# ESP32_PSU.net
KiCad netlist of a schematic drawn in EAGLE
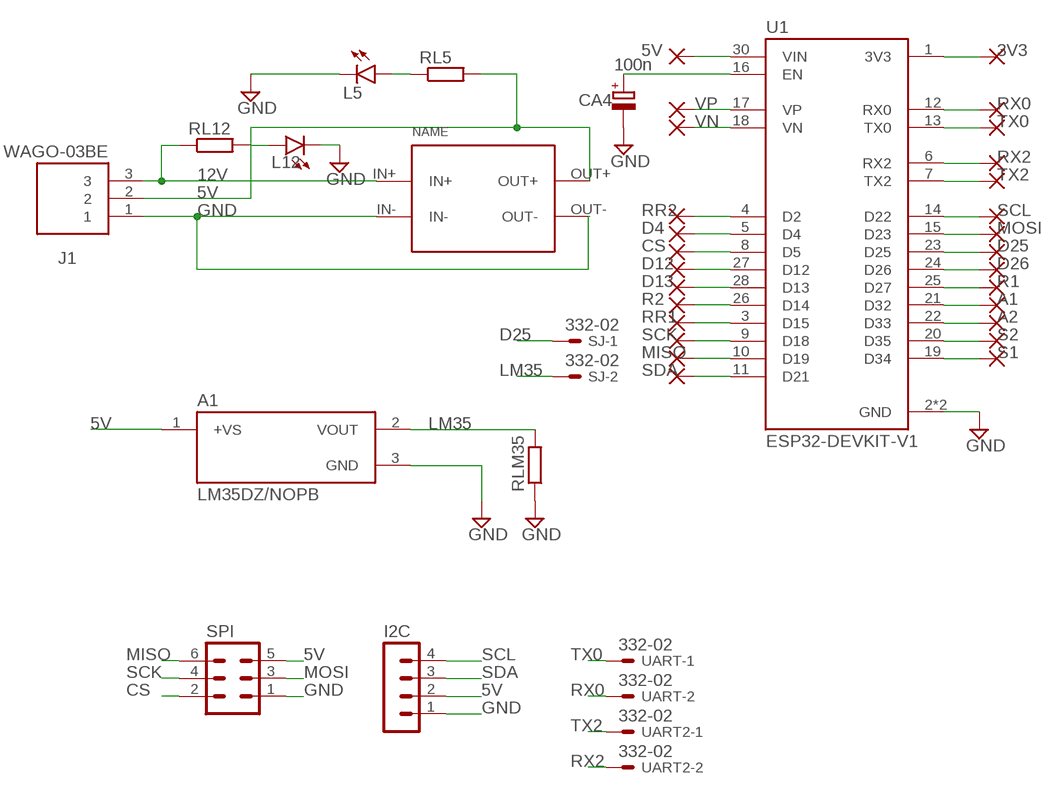
[diagram p0: schematic, sheet 1]

(export (version "E")
  (design (tool "Eeschema 10.0.6"))
  (components
    (comp (ref "A1")
      (value "LM35DZ/NOPB")
      (footprint "eagle-import:TO92127P521H735-3")
      (fields (field (name "DIGIKEY_PART_NUMBER") "LM35DZ/NOPB-ND") (field (name "MF") "Texas"))
      (libsource (lib "eagle-import") (part "LM35DZ/NOPB"))
    )
    (comp (ref "CA4")
      (value "100n")
      (footprint "eagle-import:E5-6")
      (libsource (lib "eagle-import") (part "CPOL-EUE5-6"))
    )
    (comp (ref "I2C")
      (value "MA04-1")
      (footprint "eagle-import:MA04-1")
      (libsource (lib "eagle-import") (part "MA04-1"))
    )
    (comp (ref "J1")
      (value "WAGO-03BE")
      (footprint "eagle-import:CUI_TB006-508-03BE")
      (fields (field (name "MF") "Same Sky") (field (name "MP") "TB006-508-03BE"))
      (libsource (lib "eagle-import") (part "WAGO-03BE"))
    )
    (comp (ref "L5")
      (value "LED3MM")
      (footprint "eagle-import:LED3MM")
      (libsource (lib "eagle-import") (part "LED3MM"))
    )
    (comp (ref "L12")
      (value "LED3MM")
      (footprint "eagle-import:LED3MM")
      (libsource (lib "eagle-import") (part "LED3MM"))
    )
    (comp (ref "PAD1")
      (value "WIREPAD1,6/0,9")
      (footprint "eagle-import:1,6_0,9")
      (libsource (lib "eagle-import") (part "WIREPAD1,6/0,9"))
    )
    (comp (ref "PAD2")
      (value "WIREPAD1,6/0,9")
      (footprint "eagle-import:1,6_0,9")
      (libsource (lib "eagle-import") (part "WIREPAD1,6/0,9"))
    )
    (comp (ref "PAD3")
      (value "WIREPAD1,6/0,9")
      (footprint "eagle-import:1,6_0,9")
      (libsource (lib "eagle-import") (part "WIREPAD1,6/0,9"))
    )
    (comp (ref "PAD4")
      (value "WIREPAD1,6/0,9")
      (footprint "eagle-import:1,6_0,9")
      (libsource (lib "eagle-import") (part "WIREPAD1,6/0,9"))
    )
    (comp (ref "PAD5")
      (value "WIREPAD1,6/0,9")
      (footprint "eagle-import:1,6_0,9")
      (libsource (lib "eagle-import") (part "WIREPAD1,6/0,9"))
    )
    (comp (ref "PAD6")
      (value "WIREPAD1,6/0,9")
      (footprint "eagle-import:1,6_0,9")
      (libsource (lib "eagle-import") (part "WIREPAD1,6/0,9"))
    )
    (comp (ref "PAD7")
      (value "WIREPAD1,6/0,9")
      (footprint "eagle-import:1,6_0,9")
      (libsource (lib "eagle-import") (part "WIREPAD1,6/0,9"))
    )
    (comp (ref "PAD8")
      (value "WIREPAD1,6/0,9")
      (footprint "eagle-import:1,6_0,9")
      (libsource (lib "eagle-import") (part "WIREPAD1,6/0,9"))
    )
    (comp (ref "PAD9")
      (value "WIREPAD1,6/0,9")
      (footprint "eagle-import:1,6_0,9")
      (libsource (lib "eagle-import") (part "WIREPAD1,6/0,9"))
    )
    (comp (ref "PAD10")
      (value "WIREPAD1,6/0,9")
      (footprint "eagle-import:1,6_0,9")
      (libsource (lib "eagle-import") (part "WIREPAD1,6/0,9"))
    )
    (comp (ref "PAD11")
      (value "WIREPAD1,6/0,9")
      (footprint "eagle-import:1,6_0,9")
      (libsource (lib "eagle-import") (part "WIREPAD1,6/0,9"))
    )
    (comp (ref "PAD12")
      (value "WIREPAD1,6/0,9")
      (footprint "eagle-import:1,6_0,9")
      (libsource (lib "eagle-import") (part "WIREPAD1,6/0,9"))
    )
    (comp (ref "PAD13")
      (value "WIREPAD1,6/0,9")
      (footprint "eagle-import:1,6_0,9")
      (libsource (lib "eagle-import") (part "WIREPAD1,6/0,9"))
    )
    (comp (ref "PAD14")
      (value "WIREPAD1,6/0,9")
      (footprint "eagle-import:1,6_0,9")
      (libsource (lib "eagle-import") (part "WIREPAD1,6/0,9"))
    )
    (comp (ref "PAD15")
      (value "WIREPAD1,6/0,9")
      (footprint "eagle-import:1,6_0,9")
      (libsource (lib "eagle-import") (part "WIREPAD1,6/0,9"))
    )
    (comp (ref "PAD16")
      (value "WIREPAD1,6/0,9")
      (footprint "eagle-import:1,6_0,9")
      (libsource (lib "eagle-import") (part "WIREPAD1,6/0,9"))
    )
    (comp (ref "PAD17")
      (value "WIREPAD1,6/0,9")
      (footprint "eagle-import:1,6_0,9")
      (libsource (lib "eagle-import") (part "WIREPAD1,6/0,9"))
    )
    (comp (ref "PAD18")
      (value "WIREPAD1,6/0,9")
      (footprint "eagle-import:1,6_0,9")
      (libsource (lib "eagle-import") (part "WIREPAD1,6/0,9"))
    )
    (comp (ref "PAD19")
      (value "WIREPAD1,6/0,9")
      (footprint "eagle-import:1,6_0,9")
      (libsource (lib "eagle-import") (part "WIREPAD1,6/0,9"))
    )
    (comp (ref "PAD20")
      (value "WIREPAD1,6/0,9")
      (footprint "eagle-import:1,6_0,9")
      (libsource (lib "eagle-import") (part "WIREPAD1,6/0,9"))
    )
    (comp (ref "PAD21")
      (value "WIREPAD1,6/0,9")
      (footprint "eagle-import:1,6_0,9")
      (libsource (lib "eagle-import") (part "WIREPAD1,6/0,9"))
    )
    (comp (ref "PAD22")
      (value "WIREPAD1,6/0,9")
      (footprint "eagle-import:1,6_0,9")
      (libsource (lib "eagle-import") (part "WIREPAD1,6/0,9"))
    )
    (comp (ref "PAD23")
      (value "WIREPAD1,6/0,9")
      (footprint "eagle-import:1,6_0,9")
      (libsource (lib "eagle-import") (part "WIREPAD1,6/0,9"))
    )
    (comp (ref "PAD24")
      (value "WIREPAD1,6/0,9")
      (footprint "eagle-import:1,6_0,9")
      (libsource (lib "eagle-import") (part "WIREPAD1,6/0,9"))
    )
    (comp (ref "PAD25")
      (value "WIREPAD1,6/0,9")
      (footprint "eagle-import:1,6_0,9")
      (libsource (lib "eagle-import") (part "WIREPAD1,6/0,9"))
    )
    (comp (ref "PAD26")
      (value "WIREPAD1,6/0,9")
      (footprint "eagle-import:1,6_0,9")
      (libsource (lib "eagle-import") (part "WIREPAD1,6/0,9"))
    )
    (comp (ref "PAD52")
      (value "WIREPAD1,6/0,9")
      (footprint "eagle-import:1,6_0,9")
      (libsource (lib "eagle-import") (part "WIREPAD1,6/0,9"))
    )
    (comp (ref "RL5")
      (value "R-EU_0309/12")
      (footprint "eagle-import:0309_12")
      (libsource (lib "eagle-import") (part "R-EU_0309/12"))
    )
    (comp (ref "RL12")
      (value "R-EU_0309/12")
      (footprint "eagle-import:0309_12")
      (libsource (lib "eagle-import") (part "R-EU_0309/12"))
    )
    (comp (ref "RLM35")
      (value "R-EU_0309/12")
      (footprint "eagle-import:0309_12")
      (libsource (lib "eagle-import") (part "R-EU_0309/12"))
    )
    (comp (ref "SJ")
      (value "332-02")
      (footprint "eagle-import:332-02")
      (libsource (lib "eagle-import") (part "332-02"))
    )
    (comp (ref "SPI")
      (value "MA03-2")
      (footprint "eagle-import:MA03-2")
      (libsource (lib "eagle-import") (part "MA03-2"))
    )
    (comp (ref "U$1")
      (value "CP8-ADJ")
      (footprint "eagle-import:CP8-ADJ")
      (libsource (lib "eagle-import") (part "CP8-ADJ"))
    )
    (comp (ref "U1")
      (value "ESP32-DEVKIT-V1")
      (footprint "eagle-import:MODULE_ESP32_DEVKIT_V1")
      (fields (field (name "MF") "Do it"))
      (libsource (lib "eagle-import") (part "ESP32-DEVKIT-V1"))
    )
    (comp (ref "UART")
      (value "332-02")
      (footprint "eagle-import:332-02")
      (libsource (lib "eagle-import") (part "332-02"))
    )
    (comp (ref "UART2")
      (value "332-02")
      (footprint "eagle-import:332-02")
      (libsource (lib "eagle-import") (part "332-02"))
    )
  )
  (nets
    (net (code "1") (name "/3V3") (class "Default")
      (node (ref "PAD11") (pin "1") (pinfunction "P_1") (pintype "passive"))
      (node (ref "U1") (pin "1") (pinfunction "3V3_1") (pintype "output"))
    )
    (net (code "2") (name "/5V") (class "Default")
      (node (ref "A1") (pin "1") (pinfunction "+VS_1") (pintype "power_in"))
      (node (ref "I2C") (pin "2") (pinfunction "2_2") (pintype "passive"))
      (node (ref "J1") (pin "2") (pinfunction "2_2") (pintype "passive"))
      (node (ref "PAD25") (pin "1") (pinfunction "P_1") (pintype "passive"))
      (node (ref "RL5") (pin "2") (pinfunction "2_2") (pintype "passive"))
      (node (ref "SPI") (pin "5") (pinfunction "5_5") (pintype "passive"))
      (node (ref "U$1") (pin "OUT+") (pinfunction "OUT+_OUT+") (pintype "passive"))
      (node (ref "U1") (pin "30") (pinfunction "VIN_30") (pintype "input"))
    )
    (net (code "3") (name "/12V") (class "Default")
      (node (ref "J1") (pin "3") (pinfunction "3_3") (pintype "passive"))
      (node (ref "RL12") (pin "1") (pinfunction "1_1") (pintype "passive"))
      (node (ref "U$1") (pin "IN+") (pinfunction "IN+_IN+") (pintype "passive"))
    )
    (net (code "4") (name "/A1") (class "Default")
      (node (ref "PAD21") (pin "1") (pinfunction "P_1") (pintype "passive"))
      (node (ref "U1") (pin "21") (pinfunction "D32_21") (pintype "bidirectional"))
    )
    (net (code "5") (name "/A2") (class "Default")
      (node (ref "PAD22") (pin "1") (pinfunction "P_1") (pintype "passive"))
      (node (ref "U1") (pin "22") (pinfunction "D33_22") (pintype "bidirectional"))
    )
    (net (code "6") (name "/CS") (class "Default")
      (node (ref "PAD3") (pin "1") (pinfunction "P_1") (pintype "passive"))
      (node (ref "SPI") (pin "2") (pinfunction "2_2") (pintype "passive"))
      (node (ref "U1") (pin "8") (pinfunction "D5_8") (pintype "bidirectional"))
    )
    (net (code "7") (name "/D4") (class "Default")
      (node (ref "PAD2") (pin "1") (pinfunction "P_1") (pintype "passive"))
      (node (ref "U1") (pin "5") (pinfunction "D4_5") (pintype "bidirectional"))
    )
    (net (code "8") (name "/D12") (class "Default")
      (node (ref "PAD4") (pin "1") (pinfunction "P_1") (pintype "passive"))
      (node (ref "U1") (pin "27") (pinfunction "D12_27") (pintype "bidirectional"))
    )
    (net (code "9") (name "/D13") (class "Default")
      (node (ref "PAD5") (pin "1") (pinfunction "P_1") (pintype "passive"))
      (node (ref "U1") (pin "28") (pinfunction "D13_28") (pintype "bidirectional"))
    )
    (net (code "10") (name "/D25") (class "Default")
      (node (ref "PAD18") (pin "1") (pinfunction "P_1") (pintype "passive"))
      (node (ref "SJ") (pin "1") (pinfunction "S_1") (pintype "passive"))
      (node (ref "U1") (pin "23") (pinfunction "D25_23") (pintype "bidirectional"))
    )
    (net (code "11") (name "/D26") (class "Default")
      (node (ref "PAD19") (pin "1") (pinfunction "P_1") (pintype "passive"))
      (node (ref "U1") (pin "24") (pinfunction "D26_24") (pintype "bidirectional"))
    )
    (net (code "12") (name "/LM35") (class "Default")
      (node (ref "A1") (pin "2") (pinfunction "VOUT_2") (pintype "output"))
      (node (ref "RLM35") (pin "2") (pinfunction "2_2") (pintype "passive"))
      (node (ref "SJ") (pin "2") (pinfunction "S_2") (pintype "passive"))
    )
    (net (code "13") (name "/MISO") (class "Default")
      (node (ref "PAD9") (pin "1") (pinfunction "P_1") (pintype "passive"))
      (node (ref "SPI") (pin "6") (pinfunction "6_6") (pintype "passive"))
      (node (ref "U1") (pin "10") (pinfunction "D19_10") (pintype "bidirectional"))
    )
    (net (code "14") (name "/MOSI") (class "Default")
      (node (ref "PAD17") (pin "1") (pinfunction "P_1") (pintype "passive"))
      (node (ref "SPI") (pin "3") (pinfunction "3_3") (pintype "passive"))
      (node (ref "U1") (pin "15") (pinfunction "D23_15") (pintype "bidirectional"))
    )
    (net (code "15") (name "/R1") (class "Default")
      (node (ref "PAD20") (pin "1") (pinfunction "P_1") (pintype "passive"))
      (node (ref "U1") (pin "25") (pinfunction "D27_25") (pintype "bidirectional"))
    )
    (net (code "16") (name "/R2") (class "Default")
      (node (ref "PAD6") (pin "1") (pinfunction "P_1") (pintype "passive"))
      (node (ref "U1") (pin "26") (pinfunction "D14_26") (pintype "bidirectional"))
    )
    (net (code "17") (name "/RR1") (class "Default")
      (node (ref "PAD7") (pin "1") (pinfunction "P_1") (pintype "passive"))
      (node (ref "U1") (pin "3") (pinfunction "D15_3") (pintype "bidirectional"))
    )
    (net (code "18") (name "/RR2") (class "Default")
      (node (ref "PAD1") (pin "1") (pinfunction "P_1") (pintype "passive"))
      (node (ref "U1") (pin "4") (pinfunction "D2_4") (pintype "bidirectional"))
    )
    (net (code "19") (name "/RX0") (class "Default")
      (node (ref "PAD12") (pin "1") (pinfunction "P_1") (pintype "passive"))
      (node (ref "U1") (pin "12") (pinfunction "RX0_12") (pintype "input"))
      (node (ref "UART") (pin "2") (pinfunction "S_2") (pintype "passive"))
    )
    (net (code "20") (name "/RX2") (class "Default")
      (node (ref "PAD14") (pin "1") (pinfunction "P_1") (pintype "passive"))
      (node (ref "U1") (pin "6") (pinfunction "RX2_6") (pintype "input"))
      (node (ref "UART2") (pin "2") (pinfunction "S_2") (pintype "passive"))
    )
    (net (code "21") (name "/S1") (class "Default")
      (node (ref "PAD24") (pin "1") (pinfunction "P_1") (pintype "passive"))
      (node (ref "U1") (pin "19") (pinfunction "D34_19") (pintype "bidirectional"))
    )
    (net (code "22") (name "/S2") (class "Default")
      (node (ref "PAD23") (pin "1") (pinfunction "P_1") (pintype "passive"))
      (node (ref "U1") (pin "20") (pinfunction "D35_20") (pintype "bidirectional"))
    )
    (net (code "23") (name "/SCK") (class "Default")
      (node (ref "PAD8") (pin "1") (pinfunction "P_1") (pintype "passive"))
      (node (ref "SPI") (pin "4") (pinfunction "4_4") (pintype "passive"))
      (node (ref "U1") (pin "9") (pinfunction "D18_9") (pintype "bidirectional"))
    )
    (net (code "24") (name "/SCL") (class "Default")
      (node (ref "I2C") (pin "4") (pinfunction "4_4") (pintype "passive"))
      (node (ref "PAD16") (pin "1") (pinfunction "P_1") (pintype "passive"))
      (node (ref "U1") (pin "14") (pinfunction "D22_14") (pintype "bidirectional"))
    )
    (net (code "25") (name "/SDA") (class "Default")
      (node (ref "I2C") (pin "3") (pinfunction "3_3") (pintype "passive"))
      (node (ref "PAD10") (pin "1") (pinfunction "P_1") (pintype "passive"))
      (node (ref "U1") (pin "11") (pinfunction "D21_11") (pintype "bidirectional"))
    )
    (net (code "26") (name "/TX0") (class "Default")
      (node (ref "PAD13") (pin "1") (pinfunction "P_1") (pintype "passive"))
      (node (ref "U1") (pin "13") (pinfunction "TX0_13") (pintype "output"))
      (node (ref "UART") (pin "1") (pinfunction "S_1") (pintype "passive"))
    )
    (net (code "27") (name "/TX2") (class "Default")
      (node (ref "PAD15") (pin "1") (pinfunction "P_1") (pintype "passive"))
      (node (ref "U1") (pin "7") (pinfunction "TX2_7") (pintype "output"))
      (node (ref "UART2") (pin "1") (pinfunction "S_1") (pintype "passive"))
    )
    (net (code "28") (name "/VN") (class "Default")
      (node (ref "PAD52") (pin "1") (pinfunction "P_1") (pintype "passive"))
      (node (ref "U1") (pin "18") (pinfunction "VN_18") (pintype "bidirectional"))
    )
    (net (code "29") (name "/VP") (class "Default")
      (node (ref "PAD26") (pin "1") (pinfunction "P_1") (pintype "passive"))
      (node (ref "U1") (pin "17") (pinfunction "VP_17") (pintype "bidirectional"))
    )
    (net (code "30") (name "GND") (class "Default")
      (node (ref "A1") (pin "3") (pinfunction "GND_3") (pintype "power_in"))
      (node (ref "CA4") (pin "-") (pinfunction "-_-") (pintype "passive"))
      (node (ref "I2C") (pin "1") (pinfunction "1_1") (pintype "passive"))
      (node (ref "J1") (pin "1") (pinfunction "1_1") (pintype "passive"))
      (node (ref "L12") (pin "K") (pinfunction "C_K") (pintype "passive"))
      (node (ref "L5") (pin "K") (pinfunction "C_K") (pintype "passive"))
      (node (ref "RLM35") (pin "1") (pinfunction "1_1") (pintype "passive"))
      (node (ref "SPI") (pin "1") (pinfunction "1_1") (pintype "passive"))
      (node (ref "U$1") (pin "IN-") (pinfunction "IN-_IN-") (pintype "passive"))
      (node (ref "U$1") (pin "OUT-") (pinfunction "OUT-_OUT-") (pintype "passive"))
      (node (ref "U1") (pin "2") (pinfunction "GND_2") (pintype "power_in"))
      (node (ref "U1") (pin "29") (pinfunction "GND_29") (pintype "power_in"))
    )
    (net (code "31") (name "Net-(L5-PadA)") (class "Default")
      (node (ref "L5") (pin "A") (pinfunction "A_A") (pintype "passive"))
      (node (ref "RL5") (pin "1") (pinfunction "1_1") (pintype "passive"))
    )
    (net (code "32") (name "Net-(L12-PadA)") (class "Default")
      (node (ref "L12") (pin "A") (pinfunction "A_A") (pintype "passive"))
      (node (ref "RL12") (pin "2") (pinfunction "2_2") (pintype "passive"))
    )
    (net (code "33") (name "Net-(U1-EN)") (class "Default")
      (node (ref "CA4") (pin "+") (pinfunction "+_+") (pintype "passive"))
      (node (ref "U1") (pin "16") (pinfunction "EN_16") (pintype "input"))
    )
  )
)
